# Fuse_Science_PDB_MCU.net
KiCad netlist of a schematic drawn in Altium Designer
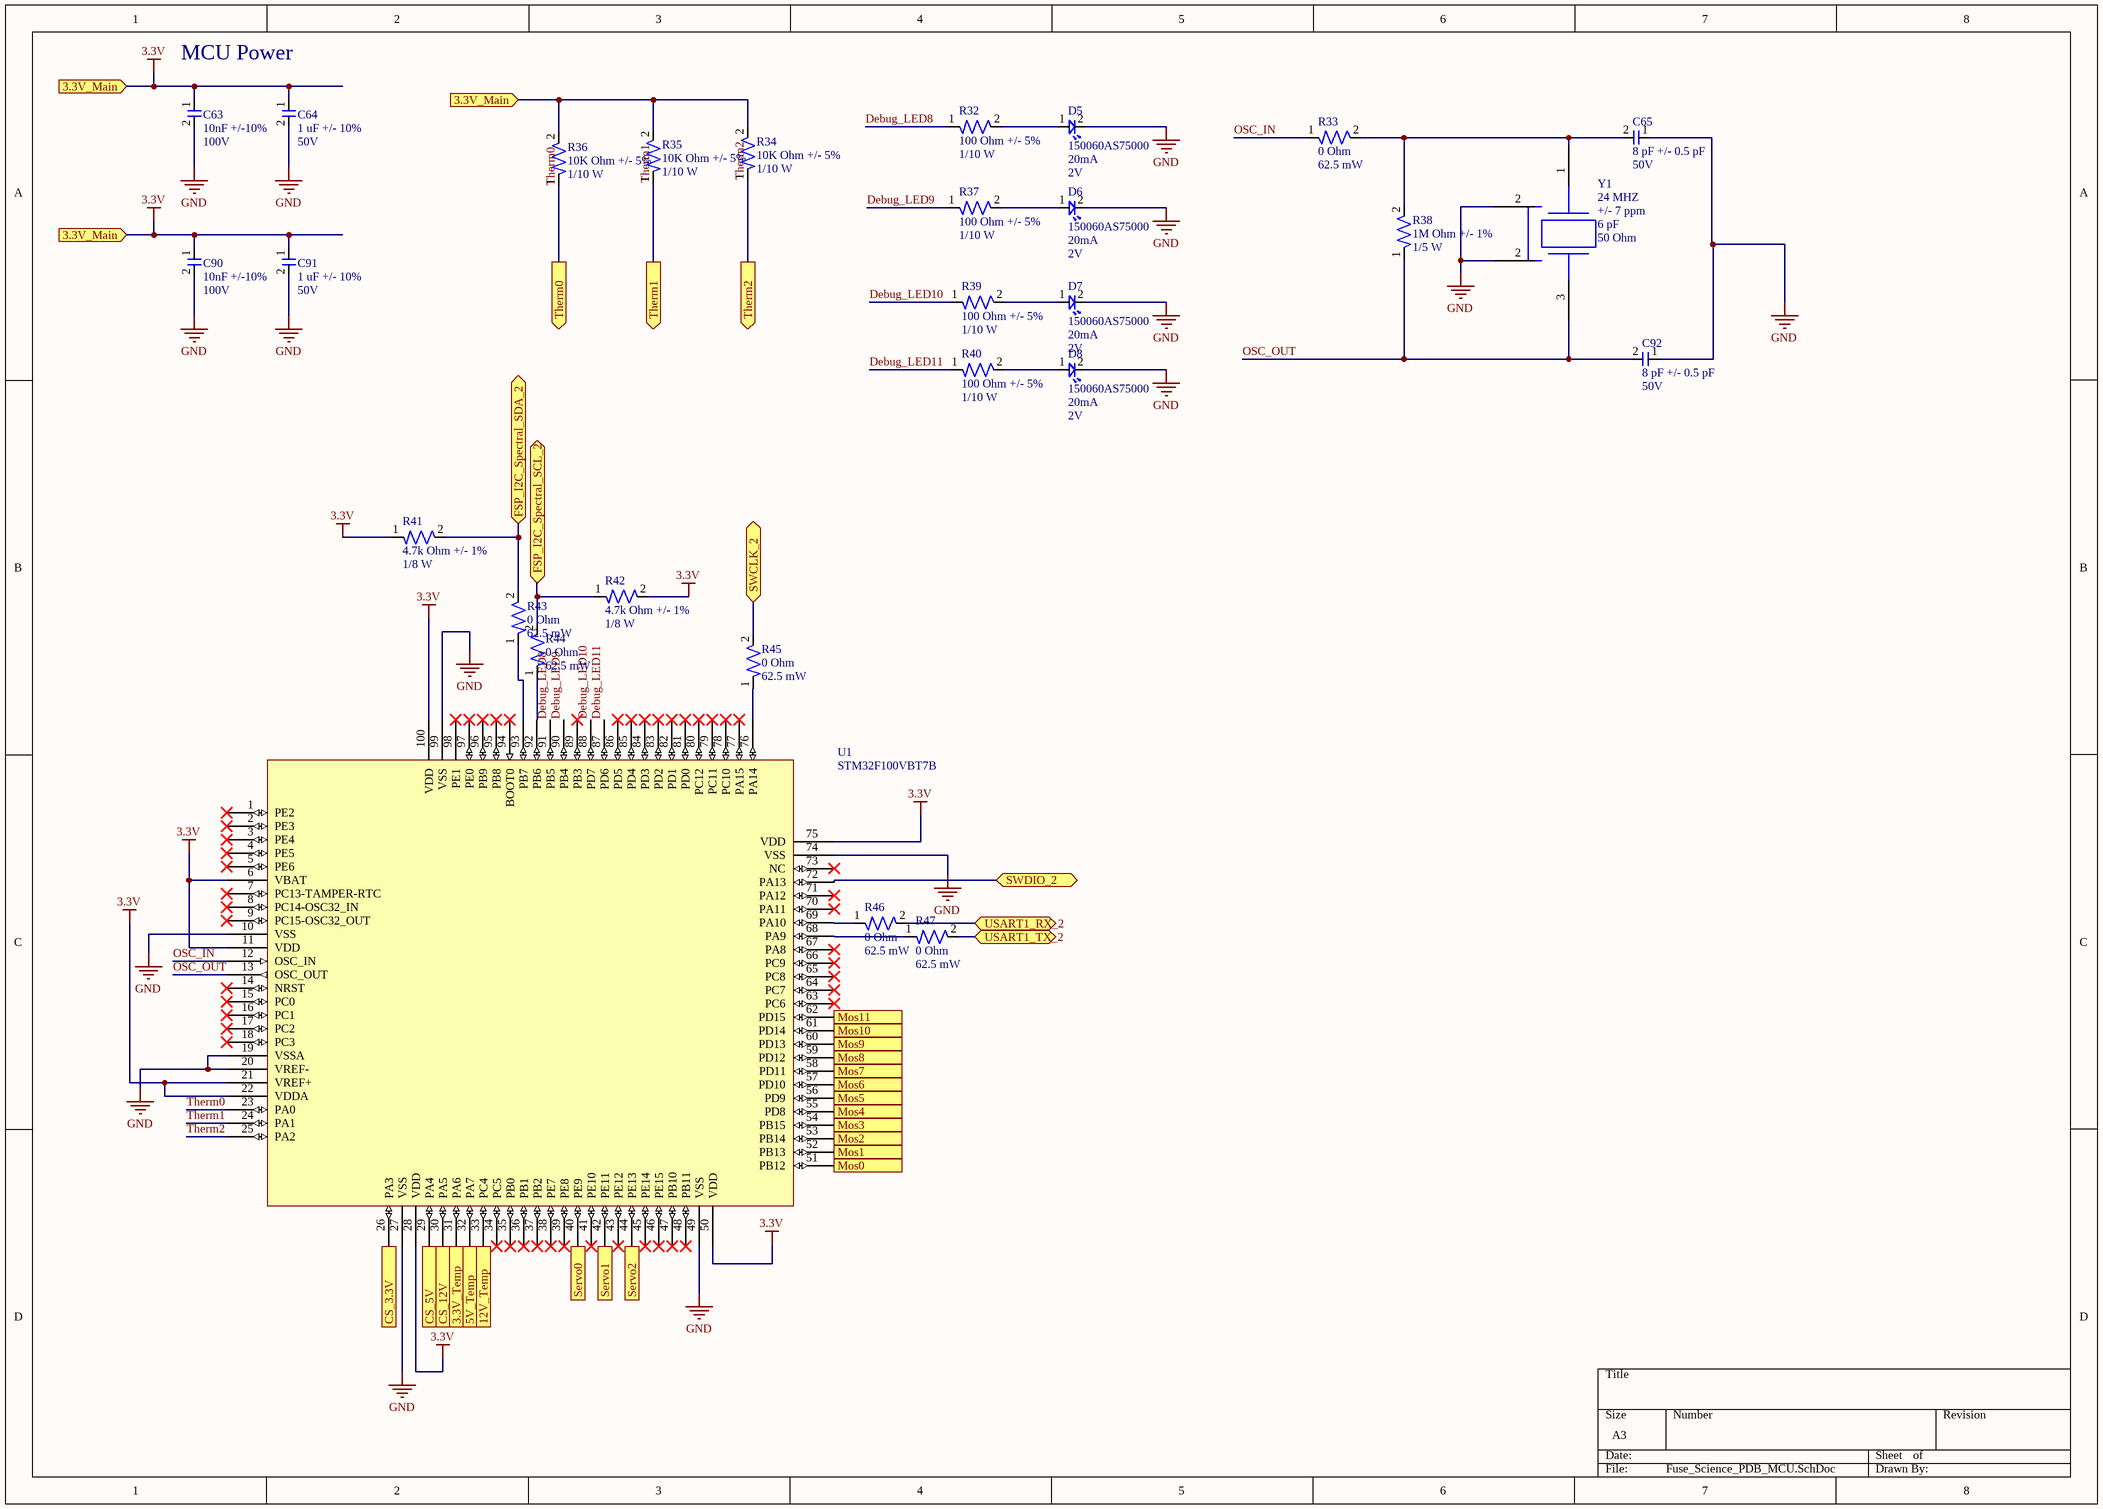
[diagram p0: Fuse_Science_PDB_MCU.SchDoc]

(export (version "E")
  (design (tool "Eeschema 10.0.6"))
  (components
    (comp (ref "C63")
      (value "CC0603KRX7R0BB103")
      (footprint "CAP-0603")
      (description "100V 10nF X7R ±10% 0603 Multilayer Ceramic Capacitors MLCC - SMD/SMT ROHS")
      (fields
        (field (name "MANUFACTURER") "Yageo")
        (field (name "JLC PART NUMBER") "C107059")
        (field (name "CAPACITANCE") "10nF +/-10%")
        (field (name "VOLTAGE RATING") "100V")
      )
      (libsource (lib "MasterLib") (part "CAP-10N-0003-JLC"))
    )
    (comp (ref "C64")
      (value "GCM21BR71H105KA03L")
      (footprint "CAP-0805")
      (description "50V 1uF X7R ±10% 0805 Multilayer Ceramic Capacitors MLCC - SMD/SMT ROHS")
      (fields
        (field (name "JLC PART NUMBER") "C126592")
        (field (name "CAP") "1 uF +/- 10%")
        (field (name "VOLTAGE") "50V")
      )
      (libsource (lib "MasterLib") (part "CAP-1U-0003-JLC"))
    )
    (comp (ref "C65")
      (value "CC0402DRNPO9BN8R0")
      (footprint "CAP-0402")
      (description "50V 8pF NP0 ±0.5pF 0402 Multilayer Ceramic Capacitors MLCC - SMD/SMT ROHS")
      (fields
        (field (name "CAPAITANCE") "8 pF +/- 0.5 pF")
        (field (name "PARAMETER 2") "50V")
        (field (name "JLC PART NUMBER") "C327227")
      )
      (libsource (lib "MasterLib") (part "CAP-8P-0002-JLC"))
    )
    (comp (ref "C90")
      (value "CC0603KRX7R0BB103")
      (footprint "CAP-0603")
      (description "100V 10nF X7R ±10% 0603 Multilayer Ceramic Capacitors MLCC - SMD/SMT ROHS")
      (fields
        (field (name "MANUFACTURER") "Yageo")
        (field (name "JLC PART NUMBER") "C107059")
        (field (name "CAPACITANCE") "10nF +/-10%")
        (field (name "VOLTAGE RATING") "100V")
      )
      (libsource (lib "MasterLib") (part "CAP-10N-0003-JLC"))
    )
    (comp (ref "C91")
      (value "GCM21BR71H105KA03L")
      (footprint "CAP-0805")
      (description "50V 1uF X7R ±10% 0805 Multilayer Ceramic Capacitors MLCC - SMD/SMT ROHS")
      (fields
        (field (name "JLC PART NUMBER") "C126592")
        (field (name "CAP") "1 uF +/- 10%")
        (field (name "VOLTAGE") "50V")
      )
      (libsource (lib "MasterLib") (part "CAP-1U-0003-JLC"))
    )
    (comp (ref "C92")
      (value "CC0402DRNPO9BN8R0")
      (footprint "CAP-0402")
      (description "50V 8pF NP0 ±0.5pF 0402 Multilayer Ceramic Capacitors MLCC - SMD/SMT ROHS")
      (fields
        (field (name "CAPAITANCE") "8 pF +/- 0.5 pF")
        (field (name "PARAMETER 2") "50V")
        (field (name "JLC PART NUMBER") "C327227")
      )
      (libsource (lib "MasterLib") (part "CAP-8P-0002-JLC"))
    )
    (comp (ref "D5")
      (value "150060AS75000")
      (footprint "LED-0603")
      (description "CAP CER 0.1UF 100V X7R 0603")
      (fields
        (field (name "MANUFACTURER") "Wurth Electronik")
        (field (name "CURRENT RATING") "20mA")
        (field (name "VF") "2V")
      )
      (libsource (lib "MasterLib") (part "LED_Amber_0001"))
    )
    (comp (ref "D6")
      (value "150060AS75000")
      (footprint "LED-0603")
      (description "CAP CER 0.1UF 100V X7R 0603")
      (fields
        (field (name "MANUFACTURER") "Wurth Electronik")
        (field (name "CURRENT RATING") "20mA")
        (field (name "VF") "2V")
      )
      (libsource (lib "MasterLib") (part "LED_Amber_0001"))
    )
    (comp (ref "D7")
      (value "150060AS75000")
      (footprint "LED-0603")
      (description "CAP CER 0.1UF 100V X7R 0603")
      (fields
        (field (name "MANUFACTURER") "Wurth Electronik")
        (field (name "CURRENT RATING") "20mA")
        (field (name "VF") "2V")
      )
      (libsource (lib "MasterLib") (part "LED_Amber_0001"))
    )
    (comp (ref "D8")
      (value "150060AS75000")
      (footprint "LED-0603")
      (description "CAP CER 0.1UF 100V X7R 0603")
      (fields
        (field (name "MANUFACTURER") "Wurth Electronik")
        (field (name "CURRENT RATING") "20mA")
        (field (name "VF") "2V")
      )
      (libsource (lib "MasterLib") (part "LED_Amber_0001"))
    )
    (comp (ref "R32")
      (value "ERJ2GEJ101X")
      (footprint "RES-0402")
      (description "100mW Thick Film Resistors ±5% ±200ppm/℃ -55℃~+155℃ 100Ω 0402  Chip Resistor - Surface Mount ROHS")
      (fields
        (field (name "RESISTANCE") "100 Ohm +/- 5%")
        (field (name "POWER") "1/10 W")
        (field (name "JLC PART NUMBER") "C412972")
      )
      (libsource (lib "MasterLib") (part "RES-100-0003-JLC"))
    )
    (comp (ref "R33")
      (value "RC0402FR-070RL")
      (footprint "RES-0402")
      (description "62.5mW Thick Film Resistors 50V -55℃~+155℃ 0Ω 0402 Chip Resistor - Surface Mount ROHS")
      (fields
        (field (name "RESISTANCE") "0 Ohm")
        (field (name "POWER") "62.5 mW")
        (field (name "JLC PART NUMBER") "C106231")
      )
      (libsource (lib "MasterLib") (part "RES-0-0002-JLC"))
    )
    (comp (ref "R34")
      (value "ERJ2GEJ103X")
      (footprint "RES-0402")
      (fields
        (field (name "RESISTANCE") "10K Ohm +/- 5%")
        (field (name "POWER") "1/10 W")
        (field (name "JLC PART NUMBER") "C278577")
      )
      (libsource (lib "MasterLib") (part "RES-10K-0003-JLC"))
    )
    (comp (ref "R35")
      (value "ERJ2GEJ103X")
      (footprint "RES-0402")
      (fields
        (field (name "RESISTANCE") "10K Ohm +/- 5%")
        (field (name "POWER") "1/10 W")
        (field (name "JLC PART NUMBER") "C278577")
      )
      (libsource (lib "MasterLib") (part "RES-10K-0003-JLC"))
    )
    (comp (ref "R36")
      (value "ERJ2GEJ103X")
      (footprint "RES-0402")
      (fields
        (field (name "RESISTANCE") "10K Ohm +/- 5%")
        (field (name "POWER") "1/10 W")
        (field (name "JLC PART NUMBER") "C278577")
      )
      (libsource (lib "MasterLib") (part "RES-10K-0003-JLC"))
    )
    (comp (ref "R37")
      (value "ERJ2GEJ101X")
      (footprint "RES-0402")
      (description "100mW Thick Film Resistors ±5% ±200ppm/℃ -55℃~+155℃ 100Ω 0402  Chip Resistor - Surface Mount ROHS")
      (fields
        (field (name "RESISTANCE") "100 Ohm +/- 5%")
        (field (name "POWER") "1/10 W")
        (field (name "JLC PART NUMBER") "C412972")
      )
      (libsource (lib "MasterLib") (part "RES-100-0003-JLC"))
    )
    (comp (ref "R38")
      (value "ERJPA2F1004X")
      (footprint "RES-0402")
      (description "1/5W ±100ppm/℃ ±1% -55℃~+155℃ 1MΩ 0402 Chip Resistor - Surface Mount ROHS")
      (fields
        (field (name "RESISTANCE") "1M Ohm +/- 1%")
        (field (name "POWER") "1/5 W")
        (field (name "JLC PART NUMBER") "C427259")
      )
      (libsource (lib "MasterLib") (part "RES-1M-0002-JLC"))
    )
    (comp (ref "R39")
      (value "ERJ2GEJ101X")
      (footprint "RES-0402")
      (description "100mW Thick Film Resistors ±5% ±200ppm/℃ -55℃~+155℃ 100Ω 0402  Chip Resistor - Surface Mount ROHS")
      (fields
        (field (name "RESISTANCE") "100 Ohm +/- 5%")
        (field (name "POWER") "1/10 W")
        (field (name "JLC PART NUMBER") "C412972")
      )
      (libsource (lib "MasterLib") (part "RES-100-0003-JLC"))
    )
    (comp (ref "R40")
      (value "ERJ2GEJ101X")
      (footprint "RES-0402")
      (description "100mW Thick Film Resistors ±5% ±200ppm/℃ -55℃~+155℃ 100Ω 0402  Chip Resistor - Surface Mount ROHS")
      (fields
        (field (name "RESISTANCE") "100 Ohm +/- 5%")
        (field (name "POWER") "1/10 W")
        (field (name "JLC PART NUMBER") "C412972")
      )
      (libsource (lib "MasterLib") (part "RES-100-0003-JLC"))
    )
    (comp (ref "R41")
      (value "RC0402FR-7W4K7L")
      (footprint "RES-0402")
      (fields
        (field (name "RESISTANCE") "4.7k Ohm +/- 1%")
        (field (name "POWER") "1/8 W")
        (field (name "JLC PART NUMBER") "C606173")
      )
      (libsource (lib "MasterLib") (part "RES-4.7K-0003-JLC"))
    )
    (comp (ref "R42")
      (value "RC0402FR-7W4K7L")
      (footprint "RES-0402")
      (fields
        (field (name "RESISTANCE") "4.7k Ohm +/- 1%")
        (field (name "POWER") "1/8 W")
        (field (name "JLC PART NUMBER") "C606173")
      )
      (libsource (lib "MasterLib") (part "RES-4.7K-0003-JLC"))
    )
    (comp (ref "R43")
      (value "RC0402FR-070RL")
      (footprint "RES-0402")
      (description "62.5mW Thick Film Resistors 50V -55℃~+155℃ 0Ω 0402 Chip Resistor - Surface Mount ROHS")
      (fields
        (field (name "RESISTANCE") "0 Ohm")
        (field (name "POWER") "62.5 mW")
        (field (name "JLC PART NUMBER") "C106231")
      )
      (libsource (lib "MasterLib") (part "RES-0-0002-JLC"))
    )
    (comp (ref "R44")
      (value "RC0402FR-070RL")
      (footprint "RES-0402")
      (description "62.5mW Thick Film Resistors 50V -55℃~+155℃ 0Ω 0402 Chip Resistor - Surface Mount ROHS")
      (fields
        (field (name "RESISTANCE") "0 Ohm")
        (field (name "POWER") "62.5 mW")
        (field (name "JLC PART NUMBER") "C106231")
      )
      (libsource (lib "MasterLib") (part "RES-0-0002-JLC"))
    )
    (comp (ref "R45")
      (value "RC0402FR-070RL")
      (footprint "RES-0402")
      (description "62.5mW Thick Film Resistors 50V -55℃~+155℃ 0Ω 0402 Chip Resistor - Surface Mount ROHS")
      (fields
        (field (name "RESISTANCE") "0 Ohm")
        (field (name "POWER") "62.5 mW")
        (field (name "JLC PART NUMBER") "C106231")
      )
      (libsource (lib "MasterLib") (part "RES-0-0002-JLC"))
    )
    (comp (ref "R46")
      (value "RC0402FR-070RL")
      (footprint "RES-0402")
      (description "62.5mW Thick Film Resistors 50V -55℃~+155℃ 0Ω 0402 Chip Resistor - Surface Mount ROHS")
      (fields
        (field (name "RESISTANCE") "0 Ohm")
        (field (name "POWER") "62.5 mW")
        (field (name "JLC PART NUMBER") "C106231")
      )
      (libsource (lib "MasterLib") (part "RES-0-0002-JLC"))
    )
    (comp (ref "R47")
      (value "RC0402FR-070RL")
      (footprint "RES-0402")
      (description "62.5mW Thick Film Resistors 50V -55℃~+155℃ 0Ω 0402 Chip Resistor - Surface Mount ROHS")
      (fields
        (field (name "RESISTANCE") "0 Ohm")
        (field (name "POWER") "62.5 mW")
        (field (name "JLC PART NUMBER") "C106231")
      )
      (libsource (lib "MasterLib") (part "RES-0-0002-JLC"))
    )
    (comp (ref "U1")
      (value "STM32F100VBT7B")
      (footprint "IC-STM32F100-0001")
      (libsource (lib "MasterLib") (part "IC-STM32F100-0001"))
    )
    (comp (ref "Y1")
      (value "ECS-240-6-37B-7KM-TR")
      (footprint "CRYSTAL-4-SMD-0001")
      (description "24 MHz ±7ppm Crystal 6pF 50 Ohms 4-SMD, No Lead")
      (fields
        (field (name "MANUFACTURER") "ECS Inc.")
        (field (name "FREQUENCY") "24 MHZ")
        (field (name "FREQUENCY TOLERANCE") "+/- 7 ppm")
        (field (name "LOAD CAPACITANCE") "6 pF")
        (field (name "EQUAVALENCE SERIES RESISTANCE") "50 Ohm")
      )
      (libsource (lib "MasterLib") (part "CRYSTAL-24MHz-0001"))
    )
  )
  (nets
    (net (code "1") (name "/3.3V_Temp") (class "Default")
      (node (ref "U1") (pin "31") (pinfunction "PA6_31") (pintype "bidirectional"))
    )
    (net (code "2") (name "/5V_Temp") (class "Default")
      (node (ref "U1") (pin "32") (pinfunction "PA7_32") (pintype "bidirectional"))
    )
    (net (code "3") (name "/12V_Temp") (class "Default")
      (node (ref "U1") (pin "33") (pinfunction "PC4_33") (pintype "bidirectional"))
    )
    (net (code "4") (name "/CS_3.3V") (class "Default")
      (node (ref "U1") (pin "26") (pinfunction "PA3_26") (pintype "bidirectional"))
    )
    (net (code "5") (name "/CS_5V") (class "Default")
      (node (ref "U1") (pin "29") (pinfunction "PA4_29") (pintype "bidirectional"))
    )
    (net (code "6") (name "/CS_12V") (class "Default")
      (node (ref "U1") (pin "30") (pinfunction "PA5_30") (pintype "bidirectional"))
    )
    (net (code "7") (name "/Debug_LED8") (class "Default")
      (node (ref "R32") (pin "1") (pinfunction "1_1") (pintype "passive"))
      (node (ref "U1") (pin "91") (pinfunction "PB5_91") (pintype "bidirectional"))
    )
    (net (code "8") (name "/Debug_LED9") (class "Default")
      (node (ref "R37") (pin "1") (pinfunction "1_1") (pintype "passive"))
      (node (ref "U1") (pin "90") (pinfunction "PB4_90") (pintype "bidirectional"))
    )
    (net (code "9") (name "/Debug_LED10") (class "Default")
      (node (ref "R39") (pin "1") (pinfunction "1_1") (pintype "passive"))
      (node (ref "U1") (pin "88") (pinfunction "PD7_88") (pintype "bidirectional"))
    )
    (net (code "10") (name "/Debug_LED11") (class "Default")
      (node (ref "R40") (pin "1") (pinfunction "1_1") (pintype "passive"))
      (node (ref "U1") (pin "87") (pinfunction "PD6_87") (pintype "bidirectional"))
    )
    (net (code "11") (name "/FSP_I2C_Spectral_SCL_2") (class "Default")
      (node (ref "R42") (pin "1") (pinfunction "1_1") (pintype "passive"))
      (node (ref "R44") (pin "2") (pinfunction "2_2") (pintype "passive"))
    )
    (net (code "12") (name "/FSP_I2C_Spectral_SDA_2") (class "Default")
      (node (ref "R41") (pin "2") (pinfunction "2_2") (pintype "passive"))
      (node (ref "R43") (pin "2") (pinfunction "2_2") (pintype "passive"))
    )
    (net (code "13") (name "/Mos0") (class "Default")
      (node (ref "U1") (pin "51") (pinfunction "PB12_51") (pintype "bidirectional"))
    )
    (net (code "14") (name "/Mos1") (class "Default")
      (node (ref "U1") (pin "52") (pinfunction "PB13_52") (pintype "bidirectional"))
    )
    (net (code "15") (name "/Mos2") (class "Default")
      (node (ref "U1") (pin "53") (pinfunction "PB14_53") (pintype "bidirectional"))
    )
    (net (code "16") (name "/Mos3") (class "Default")
      (node (ref "U1") (pin "54") (pinfunction "PB15_54") (pintype "bidirectional"))
    )
    (net (code "17") (name "/Mos4") (class "Default")
      (node (ref "U1") (pin "55") (pinfunction "PD8_55") (pintype "bidirectional"))
    )
    (net (code "18") (name "/Mos5") (class "Default")
      (node (ref "U1") (pin "56") (pinfunction "PD9_56") (pintype "bidirectional"))
    )
    (net (code "19") (name "/Mos6") (class "Default")
      (node (ref "U1") (pin "57") (pinfunction "PD10_57") (pintype "bidirectional"))
    )
    (net (code "20") (name "/Mos7") (class "Default")
      (node (ref "U1") (pin "58") (pinfunction "PD11_58") (pintype "bidirectional"))
    )
    (net (code "21") (name "/Mos8") (class "Default")
      (node (ref "U1") (pin "59") (pinfunction "PD12_59") (pintype "bidirectional"))
    )
    (net (code "22") (name "/Mos9") (class "Default")
      (node (ref "U1") (pin "60") (pinfunction "PD13_60") (pintype "bidirectional"))
    )
    (net (code "23") (name "/Mos10") (class "Default")
      (node (ref "U1") (pin "61") (pinfunction "PD14_61") (pintype "bidirectional"))
    )
    (net (code "24") (name "/Mos11") (class "Default")
      (node (ref "U1") (pin "62") (pinfunction "PD15_62") (pintype "bidirectional"))
    )
    (net (code "25") (name "/OSC_IN") (class "Default")
      (node (ref "R33") (pin "1") (pinfunction "1_1") (pintype "passive"))
      (node (ref "U1") (pin "12") (pinfunction "OSC_IN_12") (pintype "input"))
    )
    (net (code "26") (name "/OSC_OUT") (class "Default")
      (node (ref "C92") (pin "2") (pinfunction "2_2") (pintype "passive"))
      (node (ref "R38") (pin "1") (pinfunction "1_1") (pintype "passive"))
      (node (ref "U1") (pin "13") (pinfunction "OSC_OUT_13") (pintype "output"))
      (node (ref "Y1") (pin "3") (pinfunction "3_3") (pintype "passive"))
    )
    (net (code "27") (name "/SWCLK_2") (class "Default")
      (node (ref "R45") (pin "2") (pinfunction "2_2") (pintype "passive"))
    )
    (net (code "28") (name "/SWDIO_2") (class "Default")
      (node (ref "U1") (pin "72") (pinfunction "PA13_72") (pintype "bidirectional"))
    )
    (net (code "29") (name "/Servo0") (class "Default")
      (node (ref "U1") (pin "40") (pinfunction "PE9_40") (pintype "bidirectional"))
    )
    (net (code "30") (name "/Servo1") (class "Default")
      (node (ref "U1") (pin "42") (pinfunction "PE11_42") (pintype "bidirectional"))
    )
    (net (code "31") (name "/Servo2") (class "Default")
      (node (ref "U1") (pin "44") (pinfunction "PE13_44") (pintype "bidirectional"))
    )
    (net (code "32") (name "/Therm0") (class "Default")
      (node (ref "R36") (pin "1") (pinfunction "1_1") (pintype "passive"))
      (node (ref "U1") (pin "23") (pinfunction "PA0_23") (pintype "bidirectional"))
    )
    (net (code "33") (name "/Therm1") (class "Default")
      (node (ref "R35") (pin "1") (pinfunction "1_1") (pintype "passive"))
      (node (ref "U1") (pin "24") (pinfunction "PA1_24") (pintype "bidirectional"))
    )
    (net (code "34") (name "/Therm2") (class "Default")
      (node (ref "R34") (pin "1") (pinfunction "1_1") (pintype "passive"))
      (node (ref "U1") (pin "25") (pinfunction "PA2_25") (pintype "bidirectional"))
    )
    (net (code "35") (name "/USART1_RX_2") (class "Default")
      (node (ref "R46") (pin "2") (pinfunction "2_2") (pintype "passive"))
    )
    (net (code "36") (name "/USART1_TX_2") (class "Default")
      (node (ref "R47") (pin "2") (pinfunction "2_2") (pintype "passive"))
    )
    (net (code "37") (name "3.3V") (class "Default")
      (node (ref "C63") (pin "1") (pinfunction "1_1") (pintype "passive"))
      (node (ref "C64") (pin "1") (pinfunction "1_1") (pintype "passive"))
      (node (ref "C90") (pin "1") (pinfunction "1_1") (pintype "passive"))
      (node (ref "C91") (pin "1") (pinfunction "1_1") (pintype "passive"))
      (node (ref "R34") (pin "2") (pinfunction "2_2") (pintype "passive"))
      (node (ref "R35") (pin "2") (pinfunction "2_2") (pintype "passive"))
      (node (ref "R36") (pin "2") (pinfunction "2_2") (pintype "passive"))
      (node (ref "R41") (pin "1") (pinfunction "1_1") (pintype "passive"))
      (node (ref "R42") (pin "2") (pinfunction "2_2") (pintype "passive"))
      (node (ref "U1") (pin "100") (pinfunction "VDD_100") (pintype "power_in"))
      (node (ref "U1") (pin "11") (pinfunction "VDD_11") (pintype "power_in"))
      (node (ref "U1") (pin "21") (pinfunction "VREF+_21") (pintype "power_in"))
      (node (ref "U1") (pin "22") (pinfunction "VDDA_22") (pintype "power_in"))
      (node (ref "U1") (pin "28") (pinfunction "VDD_28") (pintype "power_in"))
      (node (ref "U1") (pin "50") (pinfunction "VDD_50") (pintype "power_in"))
      (node (ref "U1") (pin "6") (pinfunction "VBAT_6") (pintype "power_in"))
      (node (ref "U1") (pin "75") (pinfunction "VDD_75") (pintype "power_in"))
    )
    (net (code "38") (name "GND") (class "Default")
      (node (ref "C63") (pin "2") (pinfunction "2_2") (pintype "passive"))
      (node (ref "C64") (pin "2") (pinfunction "2_2") (pintype "passive"))
      (node (ref "C65") (pin "1") (pinfunction "1_1") (pintype "passive"))
      (node (ref "C90") (pin "2") (pinfunction "2_2") (pintype "passive"))
      (node (ref "C91") (pin "2") (pinfunction "2_2") (pintype "passive"))
      (node (ref "C92") (pin "1") (pinfunction "1_1") (pintype "passive"))
      (node (ref "D5") (pin "2") (pinfunction "2_2") (pintype "passive"))
      (node (ref "D6") (pin "2") (pinfunction "2_2") (pintype "passive"))
      (node (ref "D7") (pin "2") (pinfunction "2_2") (pintype "passive"))
      (node (ref "D8") (pin "2") (pinfunction "2_2") (pintype "passive"))
      (node (ref "U1") (pin "10") (pinfunction "VSS_10") (pintype "power_in"))
      (node (ref "U1") (pin "19") (pinfunction "VSSA_19") (pintype "power_in"))
      (node (ref "U1") (pin "20") (pinfunction "VREF-_20") (pintype "power_in"))
      (node (ref "U1") (pin "27") (pinfunction "VSS_27") (pintype "power_in"))
      (node (ref "U1") (pin "49") (pinfunction "VSS_49") (pintype "power_in"))
      (node (ref "U1") (pin "74") (pinfunction "VSS_74") (pintype "power_in"))
      (node (ref "U1") (pin "99") (pinfunction "VSS_99") (pintype "power_in"))
      (node (ref "Y1") (pin "2") (pinfunction "2_2") (pintype "passive"))
    )
    (net (code "39") (name "Net-(C65-Pad2)") (class "Default")
      (node (ref "C65") (pin "2") (pinfunction "2_2") (pintype "passive"))
      (node (ref "R33") (pin "2") (pinfunction "2_2") (pintype "passive"))
      (node (ref "R38") (pin "2") (pinfunction "2_2") (pintype "passive"))
      (node (ref "Y1") (pin "1") (pinfunction "1_1") (pintype "passive"))
    )
    (net (code "40") (name "Net-(D5-Pad1)") (class "Default")
      (node (ref "D5") (pin "1") (pinfunction "1_1") (pintype "passive"))
      (node (ref "R32") (pin "2") (pinfunction "2_2") (pintype "passive"))
    )
    (net (code "41") (name "Net-(D6-Pad1)") (class "Default")
      (node (ref "D6") (pin "1") (pinfunction "1_1") (pintype "passive"))
      (node (ref "R37") (pin "2") (pinfunction "2_2") (pintype "passive"))
    )
    (net (code "42") (name "Net-(D7-Pad1)") (class "Default")
      (node (ref "D7") (pin "1") (pinfunction "1_1") (pintype "passive"))
      (node (ref "R39") (pin "2") (pinfunction "2_2") (pintype "passive"))
    )
    (net (code "43") (name "Net-(D8-Pad1)") (class "Default")
      (node (ref "D8") (pin "1") (pinfunction "1_1") (pintype "passive"))
      (node (ref "R40") (pin "2") (pinfunction "2_2") (pintype "passive"))
    )
    (net (code "44") (name "Net-(U1-PA9)") (class "Default")
      (node (ref "R47") (pin "1") (pinfunction "1_1") (pintype "passive"))
      (node (ref "U1") (pin "68") (pinfunction "PA9_68") (pintype "bidirectional"))
    )
    (net (code "45") (name "Net-(U1-PA10)") (class "Default")
      (node (ref "R46") (pin "1") (pinfunction "1_1") (pintype "passive"))
      (node (ref "U1") (pin "69") (pinfunction "PA10_69") (pintype "bidirectional"))
    )
    (net (code "46") (name "Net-(U1-PA14)") (class "Default")
      (node (ref "R45") (pin "1") (pinfunction "1_1") (pintype "passive"))
      (node (ref "U1") (pin "76") (pinfunction "PA14_76") (pintype "bidirectional"))
    )
    (net (code "47") (name "Net-(U1-PB6)") (class "Default")
      (node (ref "R44") (pin "1") (pinfunction "1_1") (pintype "passive"))
      (node (ref "U1") (pin "92") (pinfunction "PB6_92") (pintype "bidirectional"))
    )
    (net (code "48") (name "Net-(U1-PB7)") (class "Default")
      (node (ref "R43") (pin "1") (pinfunction "1_1") (pintype "passive"))
      (node (ref "U1") (pin "93") (pinfunction "PB7_93") (pintype "bidirectional"))
    )
    (net (code "49") (name "unconnected-(U1-BOOT0-Pad94)") (class "Default")
      (node (ref "U1") (pin "94") (pinfunction "BOOT0_94") (pintype "input+no_connect"))
    )
    (net (code "50") (name "unconnected-(U1-NC-Pad73)") (class "Default")
      (node (ref "U1") (pin "73") (pinfunction "NC_73") (pintype "bidirectional+no_connect"))
    )
    (net (code "51") (name "unconnected-(U1-NRST-Pad14)") (class "Default")
      (node (ref "U1") (pin "14") (pinfunction "NRST_14") (pintype "bidirectional+no_connect"))
    )
    (net (code "52") (name "unconnected-(U1-PA8-Pad67)") (class "Default")
      (node (ref "U1") (pin "67") (pinfunction "PA8_67") (pintype "bidirectional+no_connect"))
    )
    (net (code "53") (name "unconnected-(U1-PA11-Pad70)") (class "Default")
      (node (ref "U1") (pin "70") (pinfunction "PA11_70") (pintype "bidirectional+no_connect"))
    )
    (net (code "54") (name "unconnected-(U1-PA12-Pad71)") (class "Default")
      (node (ref "U1") (pin "71") (pinfunction "PA12_71") (pintype "bidirectional+no_connect"))
    )
    (net (code "55") (name "unconnected-(U1-PA15-Pad77)") (class "Default")
      (node (ref "U1") (pin "77") (pinfunction "PA15_77") (pintype "bidirectional+no_connect"))
    )
    (net (code "56") (name "unconnected-(U1-PB0-Pad35)") (class "Default")
      (node (ref "U1") (pin "35") (pinfunction "PB0_35") (pintype "bidirectional+no_connect"))
    )
    (net (code "57") (name "unconnected-(U1-PB1-Pad36)") (class "Default")
      (node (ref "U1") (pin "36") (pinfunction "PB1_36") (pintype "bidirectional+no_connect"))
    )
    (net (code "58") (name "unconnected-(U1-PB2-Pad37)") (class "Default")
      (node (ref "U1") (pin "37") (pinfunction "PB2_37") (pintype "bidirectional+no_connect"))
    )
    (net (code "59") (name "unconnected-(U1-PB3-Pad89)") (class "Default")
      (node (ref "U1") (pin "89") (pinfunction "PB3_89") (pintype "bidirectional+no_connect"))
    )
    (net (code "60") (name "unconnected-(U1-PB8-Pad95)") (class "Default")
      (node (ref "U1") (pin "95") (pinfunction "PB8_95") (pintype "bidirectional+no_connect"))
    )
    (net (code "61") (name "unconnected-(U1-PB9-Pad96)") (class "Default")
      (node (ref "U1") (pin "96") (pinfunction "PB9_96") (pintype "bidirectional+no_connect"))
    )
    (net (code "62") (name "unconnected-(U1-PB10-Pad47)") (class "Default")
      (node (ref "U1") (pin "47") (pinfunction "PB10_47") (pintype "bidirectional+no_connect"))
    )
    (net (code "63") (name "unconnected-(U1-PB11-Pad48)") (class "Default")
      (node (ref "U1") (pin "48") (pinfunction "PB11_48") (pintype "bidirectional+no_connect"))
    )
    (net (code "64") (name "unconnected-(U1-PC0-Pad15)") (class "Default")
      (node (ref "U1") (pin "15") (pinfunction "PC0_15") (pintype "bidirectional+no_connect"))
    )
    (net (code "65") (name "unconnected-(U1-PC1-Pad16)") (class "Default")
      (node (ref "U1") (pin "16") (pinfunction "PC1_16") (pintype "bidirectional+no_connect"))
    )
    (net (code "66") (name "unconnected-(U1-PC2-Pad17)") (class "Default")
      (node (ref "U1") (pin "17") (pinfunction "PC2_17") (pintype "bidirectional+no_connect"))
    )
    (net (code "67") (name "unconnected-(U1-PC3-Pad18)") (class "Default")
      (node (ref "U1") (pin "18") (pinfunction "PC3_18") (pintype "bidirectional+no_connect"))
    )
    (net (code "68") (name "unconnected-(U1-PC5-Pad34)") (class "Default")
      (node (ref "U1") (pin "34") (pinfunction "PC5_34") (pintype "bidirectional+no_connect"))
    )
    (net (code "69") (name "unconnected-(U1-PC6-Pad63)") (class "Default")
      (node (ref "U1") (pin "63") (pinfunction "PC6_63") (pintype "bidirectional+no_connect"))
    )
    (net (code "70") (name "unconnected-(U1-PC7-Pad64)") (class "Default")
      (node (ref "U1") (pin "64") (pinfunction "PC7_64") (pintype "bidirectional+no_connect"))
    )
    (net (code "71") (name "unconnected-(U1-PC8-Pad65)") (class "Default")
      (node (ref "U1") (pin "65") (pinfunction "PC8_65") (pintype "bidirectional+no_connect"))
    )
    (net (code "72") (name "unconnected-(U1-PC9-Pad66)") (class "Default")
      (node (ref "U1") (pin "66") (pinfunction "PC9_66") (pintype "bidirectional+no_connect"))
    )
    (net (code "73") (name "unconnected-(U1-PC10-Pad78)") (class "Default")
      (node (ref "U1") (pin "78") (pinfunction "PC10_78") (pintype "bidirectional+no_connect"))
    )
    (net (code "74") (name "unconnected-(U1-PC11-Pad79)") (class "Default")
      (node (ref "U1") (pin "79") (pinfunction "PC11_79") (pintype "bidirectional+no_connect"))
    )
    (net (code "75") (name "unconnected-(U1-PC12-Pad80)") (class "Default")
      (node (ref "U1") (pin "80") (pinfunction "PC12_80") (pintype "bidirectional+no_connect"))
    )
    (net (code "76") (name "unconnected-(U1-PC13-TAMPER-RTC-Pad7)") (class "Default")
      (node (ref "U1") (pin "7") (pinfunction "PC13-TAMPER-RTC_7") (pintype "bidirectional+no_connect"))
    )
    (net (code "77") (name "unconnected-(U1-PC14-OSC32_IN-Pad8)") (class "Default")
      (node (ref "U1") (pin "8") (pinfunction "PC14-OSC32_IN_8") (pintype "bidirectional+no_connect"))
    )
    (net (code "78") (name "unconnected-(U1-PC15-OSC32_OUT-Pad9)") (class "Default")
      (node (ref "U1") (pin "9") (pinfunction "PC15-OSC32_OUT_9") (pintype "bidirectional+no_connect"))
    )
    (net (code "79") (name "unconnected-(U1-PD0-Pad81)") (class "Default")
      (node (ref "U1") (pin "81") (pinfunction "PD0_81") (pintype "bidirectional+no_connect"))
    )
    (net (code "80") (name "unconnected-(U1-PD1-Pad82)") (class "Default")
      (node (ref "U1") (pin "82") (pinfunction "PD1_82") (pintype "bidirectional+no_connect"))
    )
    (net (code "81") (name "unconnected-(U1-PD2-Pad83)") (class "Default")
      (node (ref "U1") (pin "83") (pinfunction "PD2_83") (pintype "bidirectional+no_connect"))
    )
    (net (code "82") (name "unconnected-(U1-PD3-Pad84)") (class "Default")
      (node (ref "U1") (pin "84") (pinfunction "PD3_84") (pintype "bidirectional+no_connect"))
    )
    (net (code "83") (name "unconnected-(U1-PD4-Pad85)") (class "Default")
      (node (ref "U1") (pin "85") (pinfunction "PD4_85") (pintype "bidirectional+no_connect"))
    )
    (net (code "84") (name "unconnected-(U1-PD5-Pad86)") (class "Default")
      (node (ref "U1") (pin "86") (pinfunction "PD5_86") (pintype "bidirectional+no_connect"))
    )
    (net (code "85") (name "unconnected-(U1-PE0-Pad97)") (class "Default")
      (node (ref "U1") (pin "97") (pinfunction "PE0_97") (pintype "bidirectional+no_connect"))
    )
    (net (code "86") (name "unconnected-(U1-PE1-Pad98)") (class "Default")
      (node (ref "U1") (pin "98") (pinfunction "PE1_98") (pintype "power_in+no_connect"))
    )
    (net (code "87") (name "unconnected-(U1-PE2-Pad1)") (class "Default")
      (node (ref "U1") (pin "1") (pinfunction "PE2_1") (pintype "bidirectional+no_connect"))
    )
    (net (code "88") (name "unconnected-(U1-PE3-Pad2)") (class "Default")
      (node (ref "U1") (pin "2") (pinfunction "PE3_2") (pintype "bidirectional+no_connect"))
    )
    (net (code "89") (name "unconnected-(U1-PE4-Pad3)") (class "Default")
      (node (ref "U1") (pin "3") (pinfunction "PE4_3") (pintype "bidirectional+no_connect"))
    )
    (net (code "90") (name "unconnected-(U1-PE5-Pad4)") (class "Default")
      (node (ref "U1") (pin "4") (pinfunction "PE5_4") (pintype "bidirectional+no_connect"))
    )
    (net (code "91") (name "unconnected-(U1-PE6-Pad5)") (class "Default")
      (node (ref "U1") (pin "5") (pinfunction "PE6_5") (pintype "bidirectional+no_connect"))
    )
    (net (code "92") (name "unconnected-(U1-PE7-Pad38)") (class "Default")
      (node (ref "U1") (pin "38") (pinfunction "PE7_38") (pintype "bidirectional+no_connect"))
    )
    (net (code "93") (name "unconnected-(U1-PE8-Pad39)") (class "Default")
      (node (ref "U1") (pin "39") (pinfunction "PE8_39") (pintype "bidirectional+no_connect"))
    )
    (net (code "94") (name "unconnected-(U1-PE10-Pad41)") (class "Default")
      (node (ref "U1") (pin "41") (pinfunction "PE10_41") (pintype "bidirectional+no_connect"))
    )
    (net (code "95") (name "unconnected-(U1-PE12-Pad43)") (class "Default")
      (node (ref "U1") (pin "43") (pinfunction "PE12_43") (pintype "bidirectional+no_connect"))
    )
    (net (code "96") (name "unconnected-(U1-PE14-Pad45)") (class "Default")
      (node (ref "U1") (pin "45") (pinfunction "PE14_45") (pintype "bidirectional+no_connect"))
    )
    (net (code "97") (name "unconnected-(U1-PE15-Pad46)") (class "Default")
      (node (ref "U1") (pin "46") (pinfunction "PE15_46") (pintype "bidirectional+no_connect"))
    )
  )
)
